# WiRF.net
KiCad netlist of a schematic drawn in Altium Designer
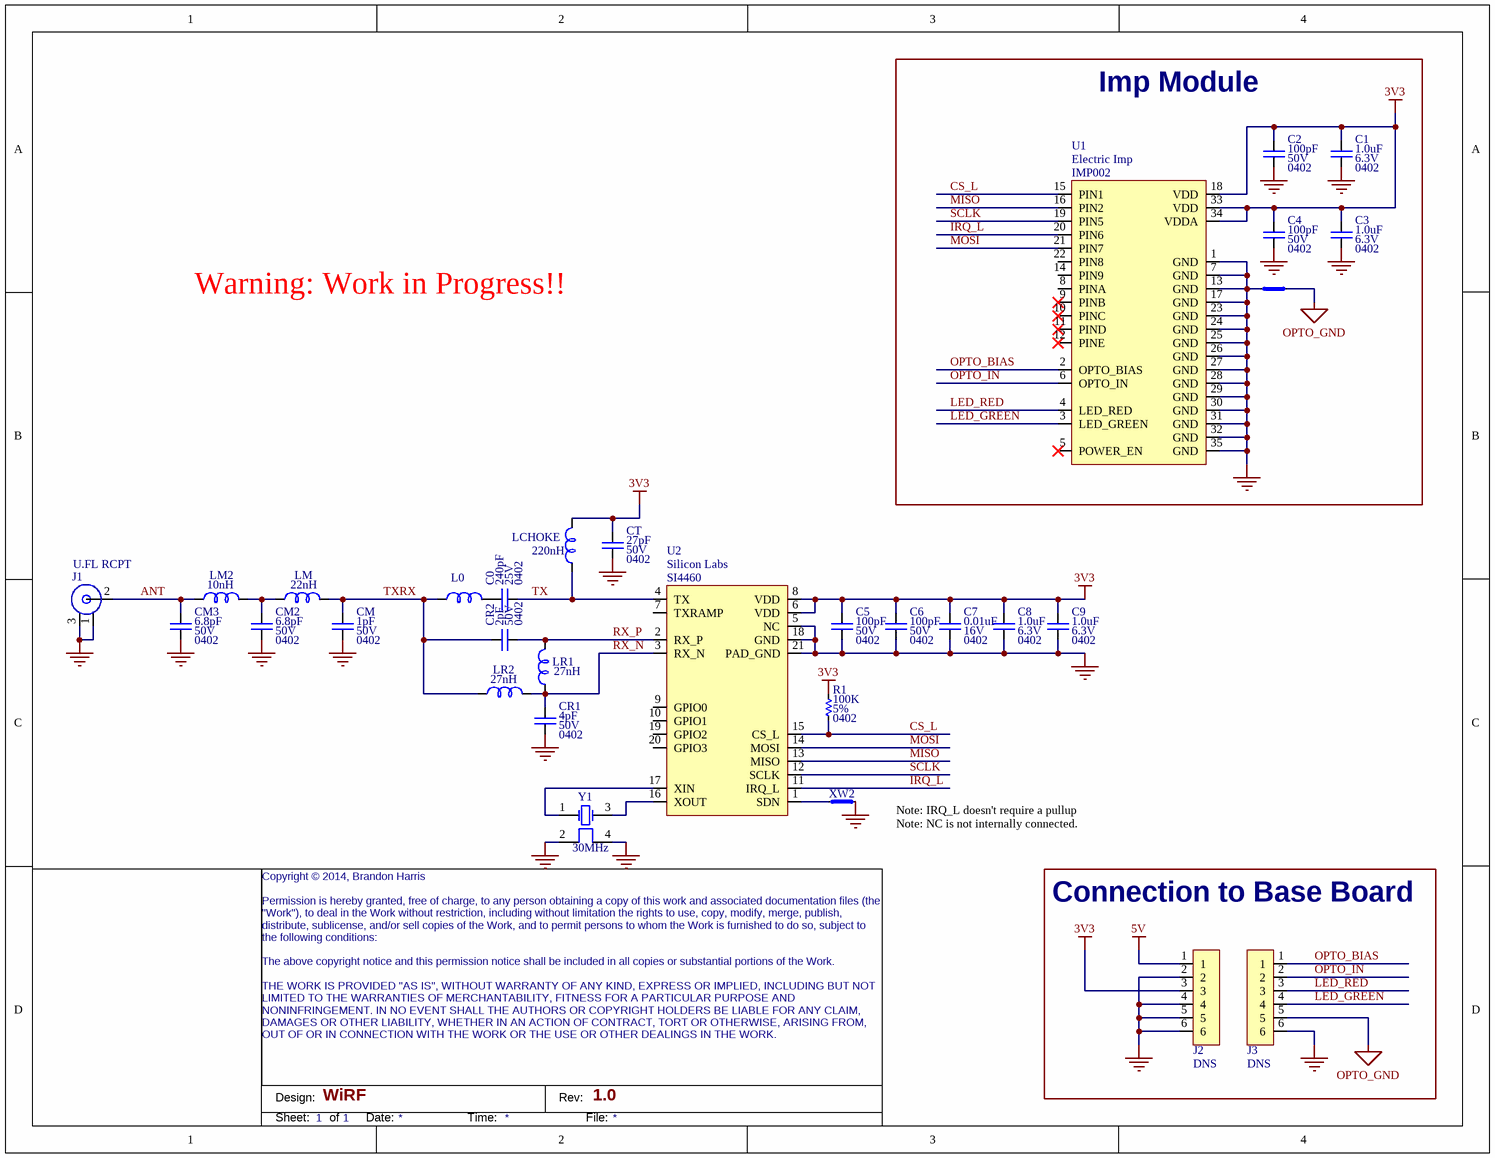
[diagram p0: WiRF.SchDoc]

(export (version "E")
  (design (tool "Eeschema 10.0.6"))
  (components
    (comp (ref "C0")
      (value "240pF")
      (footprint "CAPC1005X07N")
      (description "CAP,NP0,240pF,5%,25V,0402")
      (fields
        (field (name "TOLERANCE") "5%")
        (field (name "VOLTAGE") "25V")
        (field (name "PACKAGE") "0402")
        (field (name "PART NUMBER") "CAPC00098")
      )
      (libsource (lib "passives") (part "CAPC"))
    )
    (comp (ref "C1")
      (value "1.0uF")
      (footprint "CAPC1005X07N")
      (description "CAP,X5R,1.0uF,10%,6.3V, 0402,#")
      (fields
        (field (name "TOLERANCE") "10%")
        (field (name "VOLTAGE") "6.3V")
        (field (name "PACKAGE") "0402")
        (field (name "PART NUMBER") "CAPC00005")
      )
      (libsource (lib "passives") (part "CAPC"))
    )
    (comp (ref "C2")
      (value "100pF")
      (footprint "CAPC1005X07N")
      (description "CAP,C0G,100pF,5%,50V,0402")
      (fields
        (field (name "TOLERANCE") "5%")
        (field (name "VOLTAGE") "50V")
        (field (name "PACKAGE") "0402")
        (field (name "PART NUMBER") "CAPC00043")
      )
      (libsource (lib "passives") (part "CAPC"))
    )
    (comp (ref "C3")
      (value "1.0uF")
      (footprint "CAPC1005X07N")
      (description "CAP,X5R,1.0uF,10%,6.3V, 0402,#")
      (fields
        (field (name "TOLERANCE") "10%")
        (field (name "VOLTAGE") "6.3V")
        (field (name "PACKAGE") "0402")
        (field (name "PART NUMBER") "CAPC00005")
      )
      (libsource (lib "passives") (part "CAPC"))
    )
    (comp (ref "C4")
      (value "100pF")
      (footprint "CAPC1005X07N")
      (description "CAP,C0G,100pF,5%,50V,0402")
      (fields
        (field (name "TOLERANCE") "5%")
        (field (name "VOLTAGE") "50V")
        (field (name "PACKAGE") "0402")
        (field (name "PART NUMBER") "CAPC00043")
      )
      (libsource (lib "passives") (part "CAPC"))
    )
    (comp (ref "C5")
      (value "100pF")
      (footprint "CAPC1005X07N")
      (description "CAP,C0G,100pF,5%,50V,0402")
      (fields
        (field (name "TOLERANCE") "5%")
        (field (name "VOLTAGE") "50V")
        (field (name "PACKAGE") "0402")
        (field (name "PART NUMBER") "CAPC00043")
      )
      (libsource (lib "passives") (part "CAPC"))
    )
    (comp (ref "C6")
      (value "100pF")
      (footprint "CAPC1005X07N")
      (description "CAP,C0G,100pF,5%,50V,0402")
      (fields
        (field (name "TOLERANCE") "5%")
        (field (name "VOLTAGE") "50V")
        (field (name "PACKAGE") "0402")
        (field (name "PART NUMBER") "CAPC00043")
      )
      (libsource (lib "passives") (part "CAPC"))
    )
    (comp (ref "C7")
      (value "0.01uF")
      (footprint "CAPC1005X07N")
      (description "CAP,X7R,0.01uF,10%,16V,0402,#")
      (fields
        (field (name "TOLERANCE") "10%")
        (field (name "VOLTAGE") "16V")
        (field (name "PACKAGE") "0402")
        (field (name "PART NUMBER") "CAPC00026")
      )
      (libsource (lib "passives") (part "CAPC"))
    )
    (comp (ref "C8")
      (value "1.0uF")
      (footprint "CAPC1005X07N")
      (description "CAP,X5R,1.0uF,10%,6.3V, 0402,#")
      (fields
        (field (name "TOLERANCE") "10%")
        (field (name "VOLTAGE") "6.3V")
        (field (name "PACKAGE") "0402")
        (field (name "PART NUMBER") "CAPC00005")
      )
      (libsource (lib "passives") (part "CAPC"))
    )
    (comp (ref "C9")
      (value "1.0uF")
      (footprint "CAPC1005X07N")
      (description "CAP,X5R,1.0uF,10%,6.3V, 0402,#")
      (fields
        (field (name "TOLERANCE") "10%")
        (field (name "VOLTAGE") "6.3V")
        (field (name "PACKAGE") "0402")
        (field (name "PART NUMBER") "CAPC00005")
      )
      (libsource (lib "passives") (part "CAPC"))
    )
    (comp (ref "CM")
      (value "1pF")
      (footprint "CAPC1005X07N")
      (description "CAP,C0G,1pF,+/-0.25pF,50V,0402")
      (fields
        (field (name "TOLERANCE") "0.25p")
        (field (name "VOLTAGE") "50V")
        (field (name "PACKAGE") "0402")
        (field (name "PART NUMBER") "CAPC00081")
      )
      (libsource (lib "passives") (part "CAPC"))
    )
    (comp (ref "CM2")
      (value "6.8pF")
      (footprint "CAPC1005X07N")
      (description "CAP,C0G,6.8pF,+/-0.5pF,50V,0402")
      (fields
        (field (name "TOLERANCE") "0.5pF")
        (field (name "VOLTAGE") "50V")
        (field (name "PACKAGE") "0402")
        (field (name "PART NUMBER") "CAPC00042")
      )
      (libsource (lib "passives") (part "CAPC"))
    )
    (comp (ref "CM3")
      (value "6.8pF")
      (footprint "CAPC1005X07N")
      (description "CAP,C0G,6.8pF,+/-0.5pF,50V,0402")
      (fields
        (field (name "TOLERANCE") "0.5pF")
        (field (name "VOLTAGE") "50V")
        (field (name "PACKAGE") "0402")
        (field (name "PART NUMBER") "CAPC00042")
      )
      (libsource (lib "passives") (part "CAPC"))
    )
    (comp (ref "CR1")
      (value "4pF")
      (footprint "CAPC1005X07N")
      (description "CAP,C0G,4pF,±0.25pF,50V,0402")
      (fields
        (field (name "TOLERANCE") "0.25pF")
        (field (name "VOLTAGE") "50V")
        (field (name "PACKAGE") "0402")
        (field (name "PART NUMBER") "CAPC00093")
      )
      (libsource (lib "passives") (part "CAPC"))
    )
    (comp (ref "CR2")
      (value "2pF")
      (footprint "CAPC1005X07N")
      (description "CAP,C0G,2pF,±0.25pF,50V,0402")
      (fields
        (field (name "TOLERANCE") "0.25pF")
        (field (name "VOLTAGE") "50V")
        (field (name "PACKAGE") "0402")
        (field (name "PART NUMBER") "CAPC00100")
      )
      (libsource (lib "passives") (part "CAPC"))
    )
    (comp (ref "CT")
      (value "27pF")
      (footprint "CAPC1005X07N")
      (description "CAP,C0G,27pF,5%,50V,0402")
      (fields
        (field (name "TOLERANCE") "5%")
        (field (name "VOLTAGE") "50V")
        (field (name "PACKAGE") "0402")
        (field (name "PART NUMBER") "CAPC00044")
      )
      (libsource (lib "passives") (part "CAPC"))
    )
    (comp (ref "J1")
      (value "U.FL RCPT")
      (footprint "RF_RCPT_UFL_400X400")
      (description "Conn, Coax, U.FL, non-switch, Rcpt, 2.6 x 2.5mm, SMD")
      (fields (field (name "PART NUMBER") "CON00013") (field (name "MANUFACTURER") "Hirose"))
      (libsource (lib "connectors") (part "RF_UFL_RCPT"))
    )
    (comp (ref "J2")
      (value "Header")
      (footprint "HDR254P1X6-N:HDR254P1X6-N")
      (description "Spacer, 1x6 Pin, 2.54mm Pitch, 0.661\" Stack Height, Vertical, Through Hole")
      (fields
        (field (name "PART NUMBER") "HDR00020")
        (field (name "MANUFACTURER") "Harwin")
        (field (name "BOMOPTION") "DNS")
      )
      (libsource (lib "") (part "HDR1X6_1"))
    )
    (comp (ref "J3")
      (value "Header")
      (footprint "HDR254P1X6-N:HDR254P1X6-N")
      (description "Spacer, 1x6 Pin, 2.54mm Pitch, 0.661\" Stack Height, Vertical, Through Hole")
      (fields
        (field (name "PART NUMBER") "HDR00020")
        (field (name "MANUFACTURER") "Harwin")
        (field (name "BOMOPTION") "DNS")
      )
      (libsource (lib "discretes") (part "HDR1X6"))
    )
    (comp (ref "L0")
      (value "Inductor")
      (footprint "INDC2520X23N")
      (description "IND, 220nH, 10%, 500mA, 280 mOhm, 2520")
      (fields (field (name "PART NUMBER") "IND00009") (field (name "TOLERANCE") "10%"))
      (libsource (lib "passives") (part "INDUCTOR"))
    )
    (comp (ref "LCHOKE")
      (value "220nH")
      (footprint "INDC2520X23N")
      (description "IND, 220nH, 10%, 500mA, 280 mOhm, 2520")
      (fields (field (name "PART NUMBER") "IND00009") (field (name "TOLERANCE") "10%"))
      (libsource (lib "passives") (part "INDUCTOR"))
    )
    (comp (ref "LM")
      (value "22nH")
      (footprint "INDC1005X06N")
      (description "IND, 22nH, 5%, 300mA, 600 mOhm, 0402")
      (fields (field (name "PART NUMBER") "IND00036") (field (name "TOLERANCE") "5%"))
      (libsource (lib "passives") (part "INDUCTOR"))
    )
    (comp (ref "LM2")
      (value "10nH")
      (footprint "INDC1005X06N")
      (description "IND, 10nH, 5%, 340mA, 310 mOhm, 1005")
      (fields (field (name "PART NUMBER") "IND00008") (field (name "TOLERANCE") "5%"))
      (libsource (lib "passives") (part "INDUCTOR"))
    )
    (comp (ref "LR1")
      (value "27nH")
      (footprint "INDC1005X06N")
      (description "IND, 27nH, 5%, 700 mOhm, 0402, 300mA")
      (fields (field (name "PART NUMBER") "IND00041") (field (name "TOLERANCE") "5%"))
      (libsource (lib "passives") (part "INDUCTOR"))
    )
    (comp (ref "LR2")
      (value "27nH")
      (footprint "INDC1005X06N")
      (description "IND, 27nH, 5%, 700 mOhm, 0402, 300mA")
      (fields (field (name "PART NUMBER") "IND00041") (field (name "TOLERANCE") "5%"))
      (libsource (lib "passives") (part "INDUCTOR"))
    )
    (comp (ref "R1")
      (value "100K")
      (footprint "RESC1005X04N")
      (description "RES,100K,5%,0.063W,0402,#")
      (fields
        (field (name "PACKAGE") "0402")
        (field (name "TOLERANCE") "5%")
        (field (name "PART NUMBER") "RES00001")
        (field (name "POWER") "0.063W")
      )
      (libsource (lib "passives") (part "RES"))
    )
    (comp (ref "U1")
      (value "imp module")
      (footprint "IMP_MODULE")
      (description "Module, Electric Imp Solder Down with Antenna")
      (fields
        (field (name "PART NUMBER") "MOD00002")
        (field (name "MANUFACTURER") "Electric Imp")
        (field (name "MANUFACTURER PART NUMBER") "IMP002")
      )
      (libsource (lib "modules") (part "IMP_MODULE"))
    )
    (comp (ref "U2")
      (value "SI446X")
      (footprint "QFN50P400X400X90_HS-21N")
      (description "IC, RF, Sub-GHz Transceiver, QFN20")
      (fields
        (field (name "PART NUMBER") "IC00162")
        (field (name "MANUFACTURER") "Silicon Labs")
        (field (name "MANUFACTURER PART NUMBER") "SI4460")
      )
      (libsource (lib "ic") (part "SI446X"))
    )
    (comp (ref "XW1")
      (value "XW Link")
      (footprint "XW1005-COVERED")
      (description "Short two wires together")
      (fields (field (name "PART NUMBER") "ELEC00008"))
      (libsource (lib "electrical") (part "XW"))
    )
    (comp (ref "XW2")
      (value "XW Link")
      (footprint "XW1005-COVERED")
      (description "Short two wires together")
      (fields (field (name "PART NUMBER") "ELEC00008"))
      (libsource (lib "electrical") (part "XW"))
    )
    (comp (ref "Y1")
      (value "XTAL_4")
      (footprint "XTAL_25X20X05-4N")
      (description "XTAL, 30MHz, 20ppm, 10pF, 2.5x2.0mm, SMD-4")
      (fields
        (field (name "PART NUMBER") "XTAL00020")
        (field (name "FREQUENCY") "30MHz")
        (field (name "MANUFACTURER") "Abracon")
      )
      (libsource (lib "xtalosc") (part "XTAL_4"))
    )
  )
  (nets
    (net (code "1") (name "/ANT") (class "Default")
      (node (ref "CM3") (pin "2") (pinfunction "2_2") (pintype "passive"))
      (node (ref "J1") (pin "2") (pinfunction "RF_2") (pintype "passive"))
      (node (ref "LM2") (pin "1") (pinfunction "1_1") (pintype "passive"))
    )
    (net (code "2") (name "/CS_L") (class "Default")
      (node (ref "R1") (pin "2") (pinfunction "2_2") (pintype "passive"))
      (node (ref "U1") (pin "15") (pinfunction "PIN1_15") (pintype "passive"))
      (node (ref "U2") (pin "15") (pinfunction "CS_L_15") (pintype "passive"))
    )
    (net (code "3") (name "/IRQ_L") (class "Default")
      (node (ref "U1") (pin "20") (pinfunction "PIN6_20") (pintype "passive"))
      (node (ref "U2") (pin "11") (pinfunction "IRQ_L_11") (pintype "passive"))
    )
    (net (code "4") (name "/LED_GREEN") (class "Default")
      (node (ref "J3") (pin "4") (pinfunction "4_4") (pintype "passive"))
      (node (ref "U1") (pin "3") (pinfunction "LED_GREEN_3") (pintype "passive"))
    )
    (net (code "5") (name "/LED_RED") (class "Default")
      (node (ref "J3") (pin "3") (pinfunction "3_3") (pintype "passive"))
      (node (ref "U1") (pin "4") (pinfunction "LED_RED_4") (pintype "passive"))
    )
    (net (code "6") (name "/MISO") (class "Default")
      (node (ref "U1") (pin "16") (pinfunction "PIN2_16") (pintype "passive"))
      (node (ref "U2") (pin "13") (pinfunction "MISO_13") (pintype "passive"))
    )
    (net (code "7") (name "/MOSI") (class "Default")
      (node (ref "U1") (pin "21") (pinfunction "PIN7_21") (pintype "passive"))
      (node (ref "U2") (pin "14") (pinfunction "MOSI_14") (pintype "passive"))
    )
    (net (code "8") (name "/OPTO_BIAS") (class "Default")
      (node (ref "J3") (pin "1") (pinfunction "1_1") (pintype "passive"))
      (node (ref "U1") (pin "2") (pinfunction "OPTO_BIAS_2") (pintype "passive"))
    )
    (net (code "9") (name "/OPTO_IN") (class "Default")
      (node (ref "J3") (pin "2") (pinfunction "2_2") (pintype "passive"))
      (node (ref "U1") (pin "6") (pinfunction "OPTO_IN_6") (pintype "passive"))
    )
    (net (code "10") (name "/RX_N") (class "Default")
      (node (ref "CR1") (pin "2") (pinfunction "2_2") (pintype "passive"))
      (node (ref "LR1") (pin "1") (pinfunction "1_1") (pintype "passive"))
      (node (ref "LR2") (pin "2") (pinfunction "2_2") (pintype "passive"))
      (node (ref "U2") (pin "3") (pinfunction "RX_N_3") (pintype "passive"))
    )
    (net (code "11") (name "/RX_P") (class "Default")
      (node (ref "CR2") (pin "1") (pinfunction "1_1") (pintype "passive"))
      (node (ref "LR1") (pin "2") (pinfunction "2_2") (pintype "passive"))
      (node (ref "U2") (pin "2") (pinfunction "RX_P_2") (pintype "passive"))
    )
    (net (code "12") (name "/SCLK") (class "Default")
      (node (ref "U1") (pin "19") (pinfunction "PIN5_19") (pintype "passive"))
      (node (ref "U2") (pin "12") (pinfunction "SCLK_12") (pintype "passive"))
    )
    (net (code "13") (name "/TX") (class "Default")
      (node (ref "C0") (pin "1") (pinfunction "1_1") (pintype "passive"))
      (node (ref "LCHOKE") (pin "1") (pinfunction "1_1") (pintype "passive"))
      (node (ref "U2") (pin "4") (pinfunction "TX_4") (pintype "passive"))
    )
    (net (code "14") (name "/TXRX") (class "Default")
      (node (ref "CM") (pin "2") (pinfunction "2_2") (pintype "passive"))
      (node (ref "CR2") (pin "2") (pinfunction "2_2") (pintype "passive"))
      (node (ref "L0") (pin "1") (pinfunction "1_1") (pintype "passive"))
      (node (ref "LM") (pin "2") (pinfunction "2_2") (pintype "passive"))
      (node (ref "LR2") (pin "1") (pinfunction "1_1") (pintype "passive"))
    )
    (net (code "15") (name "3V3") (class "Default")
      (node (ref "C1") (pin "2") (pinfunction "2_2") (pintype "passive"))
      (node (ref "C2") (pin "2") (pinfunction "2_2") (pintype "passive"))
      (node (ref "C3") (pin "2") (pinfunction "2_2") (pintype "passive"))
      (node (ref "C4") (pin "2") (pinfunction "2_2") (pintype "passive"))
      (node (ref "C5") (pin "2") (pinfunction "2_2") (pintype "passive"))
      (node (ref "C6") (pin "2") (pinfunction "2_2") (pintype "passive"))
      (node (ref "C7") (pin "2") (pinfunction "2_2") (pintype "passive"))
      (node (ref "C8") (pin "2") (pinfunction "2_2") (pintype "passive"))
      (node (ref "C9") (pin "2") (pinfunction "2_2") (pintype "passive"))
      (node (ref "CT") (pin "2") (pinfunction "2_2") (pintype "passive"))
      (node (ref "J2") (pin "3") (pinfunction "3_3") (pintype "passive"))
      (node (ref "LCHOKE") (pin "2") (pinfunction "2_2") (pintype "passive"))
      (node (ref "R1") (pin "1") (pinfunction "1_1") (pintype "passive"))
      (node (ref "U1") (pin "18") (pinfunction "VDD_18") (pintype "passive"))
      (node (ref "U1") (pin "33") (pinfunction "VDD_33") (pintype "passive"))
      (node (ref "U1") (pin "34") (pinfunction "VDDA_34") (pintype "passive"))
      (node (ref "U2") (pin "6") (pinfunction "VDD_6") (pintype "passive"))
      (node (ref "U2") (pin "8") (pinfunction "VDD_8") (pintype "passive"))
    )
    (net (code "16") (name "5V") (class "Default")
      (node (ref "J2") (pin "1") (pinfunction "1_1") (pintype "passive"))
    )
    (net (code "17") (name "GND") (class "Default")
      (node (ref "C1") (pin "1") (pinfunction "1_1") (pintype "passive"))
      (node (ref "C2") (pin "1") (pinfunction "1_1") (pintype "passive"))
      (node (ref "C3") (pin "1") (pinfunction "1_1") (pintype "passive"))
      (node (ref "C4") (pin "1") (pinfunction "1_1") (pintype "passive"))
      (node (ref "C5") (pin "1") (pinfunction "1_1") (pintype "passive"))
      (node (ref "C6") (pin "1") (pinfunction "1_1") (pintype "passive"))
      (node (ref "C7") (pin "1") (pinfunction "1_1") (pintype "passive"))
      (node (ref "C8") (pin "1") (pinfunction "1_1") (pintype "passive"))
      (node (ref "C9") (pin "1") (pinfunction "1_1") (pintype "passive"))
      (node (ref "CM") (pin "1") (pinfunction "1_1") (pintype "passive"))
      (node (ref "CM2") (pin "1") (pinfunction "1_1") (pintype "passive"))
      (node (ref "CM3") (pin "1") (pinfunction "1_1") (pintype "passive"))
      (node (ref "CR1") (pin "1") (pinfunction "1_1") (pintype "passive"))
      (node (ref "CT") (pin "1") (pinfunction "1_1") (pintype "passive"))
      (node (ref "J1") (pin "1") (pinfunction "SHLD_1") (pintype "power_in"))
      (node (ref "J1") (pin "3") (pinfunction "SHIELD_3") (pintype "passive"))
      (node (ref "J2") (pin "2") (pinfunction "2_2") (pintype "passive"))
      (node (ref "J2") (pin "4") (pinfunction "4_4") (pintype "passive"))
      (node (ref "J2") (pin "5") (pinfunction "5_5") (pintype "passive"))
      (node (ref "J2") (pin "6") (pinfunction "6_6") (pintype "passive"))
      (node (ref "J3") (pin "6") (pinfunction "6_6") (pintype "passive"))
      (node (ref "U1") (pin "1") (pinfunction "GND_1") (pintype "passive"))
      (node (ref "U1") (pin "13") (pinfunction "GND_13") (pintype "passive"))
      (node (ref "U1") (pin "17") (pinfunction "GND_17") (pintype "passive"))
      (node (ref "U1") (pin "23") (pinfunction "GND_23") (pintype "passive"))
      (node (ref "U1") (pin "24") (pinfunction "GND_24") (pintype "passive"))
      (node (ref "U1") (pin "25") (pinfunction "GND_25") (pintype "passive"))
      (node (ref "U1") (pin "26") (pinfunction "GND_26") (pintype "passive"))
      (node (ref "U1") (pin "27") (pinfunction "GND_27") (pintype "passive"))
      (node (ref "U1") (pin "28") (pinfunction "GND_28") (pintype "passive"))
      (node (ref "U1") (pin "29") (pinfunction "GND_29") (pintype "passive"))
      (node (ref "U1") (pin "30") (pinfunction "GND_30") (pintype "passive"))
      (node (ref "U1") (pin "31") (pinfunction "GND_31") (pintype "passive"))
      (node (ref "U1") (pin "32") (pinfunction "GND_32") (pintype "passive"))
      (node (ref "U1") (pin "35") (pinfunction "GND_35") (pintype "passive"))
      (node (ref "U1") (pin "7") (pinfunction "GND_7") (pintype "passive"))
      (node (ref "U2") (pin "18") (pinfunction "GND_18") (pintype "passive"))
      (node (ref "U2") (pin "21") (pinfunction "PAD_GND_21") (pintype "passive"))
      (node (ref "U2") (pin "5") (pinfunction "NC_5") (pintype "passive"))
      (node (ref "XW1") (pin "1") (pinfunction "1_1") (pintype "passive"))
      (node (ref "XW2") (pin "1") (pinfunction "1_1") (pintype "passive"))
      (node (ref "Y1") (pin "2") (pinfunction "GND_2") (pintype "passive"))
      (node (ref "Y1") (pin "4") (pinfunction "GND_4") (pintype "passive"))
    )
    (net (code "18") (name "Net-(C0-Pad2)") (class "Default")
      (node (ref "C0") (pin "2") (pinfunction "2_2") (pintype "passive"))
      (node (ref "L0") (pin "2") (pinfunction "2_2") (pintype "passive"))
    )
    (net (code "19") (name "Net-(CM2-Pad2)") (class "Default")
      (node (ref "CM2") (pin "2") (pinfunction "2_2") (pintype "passive"))
      (node (ref "LM") (pin "1") (pinfunction "1_1") (pintype "passive"))
      (node (ref "LM2") (pin "2") (pinfunction "2_2") (pintype "passive"))
    )
    (net (code "20") (name "Net-(U2-SDN)") (class "Default")
      (node (ref "U2") (pin "1") (pinfunction "SDN_1") (pintype "passive"))
      (node (ref "XW2") (pin "2") (pinfunction "2_2") (pintype "passive"))
    )
    (net (code "21") (name "Net-(U2-XIN)") (class "Default")
      (node (ref "U2") (pin "17") (pinfunction "XIN_17") (pintype "passive"))
      (node (ref "Y1") (pin "1") (pinfunction "OSC1_1") (pintype "passive"))
    )
    (net (code "22") (name "Net-(U2-XOUT)") (class "Default")
      (node (ref "U2") (pin "16") (pinfunction "XOUT_16") (pintype "passive"))
      (node (ref "Y1") (pin "3") (pinfunction "OSC2_3") (pintype "passive"))
    )
    (net (code "23") (name "OPTO_GND") (class "Default")
      (node (ref "J3") (pin "5") (pinfunction "5_5") (pintype "passive"))
      (node (ref "XW1") (pin "2") (pinfunction "2_2") (pintype "passive"))
    )
    (net (code "24") (name "unconnected-(U1-PIN8-Pad22)") (class "Default")
      (node (ref "U1") (pin "22") (pinfunction "PIN8_22") (pintype "passive"))
    )
    (net (code "25") (name "unconnected-(U1-PIN9-Pad14)") (class "Default")
      (node (ref "U1") (pin "14") (pinfunction "PIN9_14") (pintype "passive"))
    )
    (net (code "26") (name "unconnected-(U1-PINA-Pad8)") (class "Default")
      (node (ref "U1") (pin "8") (pinfunction "PINA_8") (pintype "passive"))
    )
    (net (code "27") (name "unconnected-(U1-PINB-Pad9)") (class "Default")
      (node (ref "U1") (pin "9") (pinfunction "PINB_9") (pintype "passive+no_connect"))
    )
    (net (code "28") (name "unconnected-(U1-PINC-Pad10)") (class "Default")
      (node (ref "U1") (pin "10") (pinfunction "PINC_10") (pintype "passive+no_connect"))
    )
    (net (code "29") (name "unconnected-(U1-PIND-Pad11)") (class "Default")
      (node (ref "U1") (pin "11") (pinfunction "PIND_11") (pintype "passive+no_connect"))
    )
    (net (code "30") (name "unconnected-(U1-PINE-Pad12)") (class "Default")
      (node (ref "U1") (pin "12") (pinfunction "PINE_12") (pintype "passive+no_connect"))
    )
    (net (code "31") (name "unconnected-(U1-POWER_EN-Pad5)") (class "Default")
      (node (ref "U1") (pin "5") (pinfunction "POWER_EN_5") (pintype "passive+no_connect"))
    )
    (net (code "32") (name "unconnected-(U2-GPIO0-Pad9)") (class "Default")
      (node (ref "U2") (pin "9") (pinfunction "GPIO0_9") (pintype "passive"))
    )
    (net (code "33") (name "unconnected-(U2-GPIO1-Pad10)") (class "Default")
      (node (ref "U2") (pin "10") (pinfunction "GPIO1_10") (pintype "passive"))
    )
    (net (code "34") (name "unconnected-(U2-GPIO2-Pad19)") (class "Default")
      (node (ref "U2") (pin "19") (pinfunction "GPIO2_19") (pintype "passive"))
    )
    (net (code "35") (name "unconnected-(U2-GPIO3-Pad20)") (class "Default")
      (node (ref "U2") (pin "20") (pinfunction "GPIO3_20") (pintype "passive"))
    )
    (net (code "36") (name "unconnected-(U2-TXRAMP-Pad7)") (class "Default")
      (node (ref "U2") (pin "7") (pinfunction "TXRAMP_7") (pintype "passive"))
    )
  )
)
